# Schematics_PCB.net
KiCad netlist of a schematic drawn in EAGLE
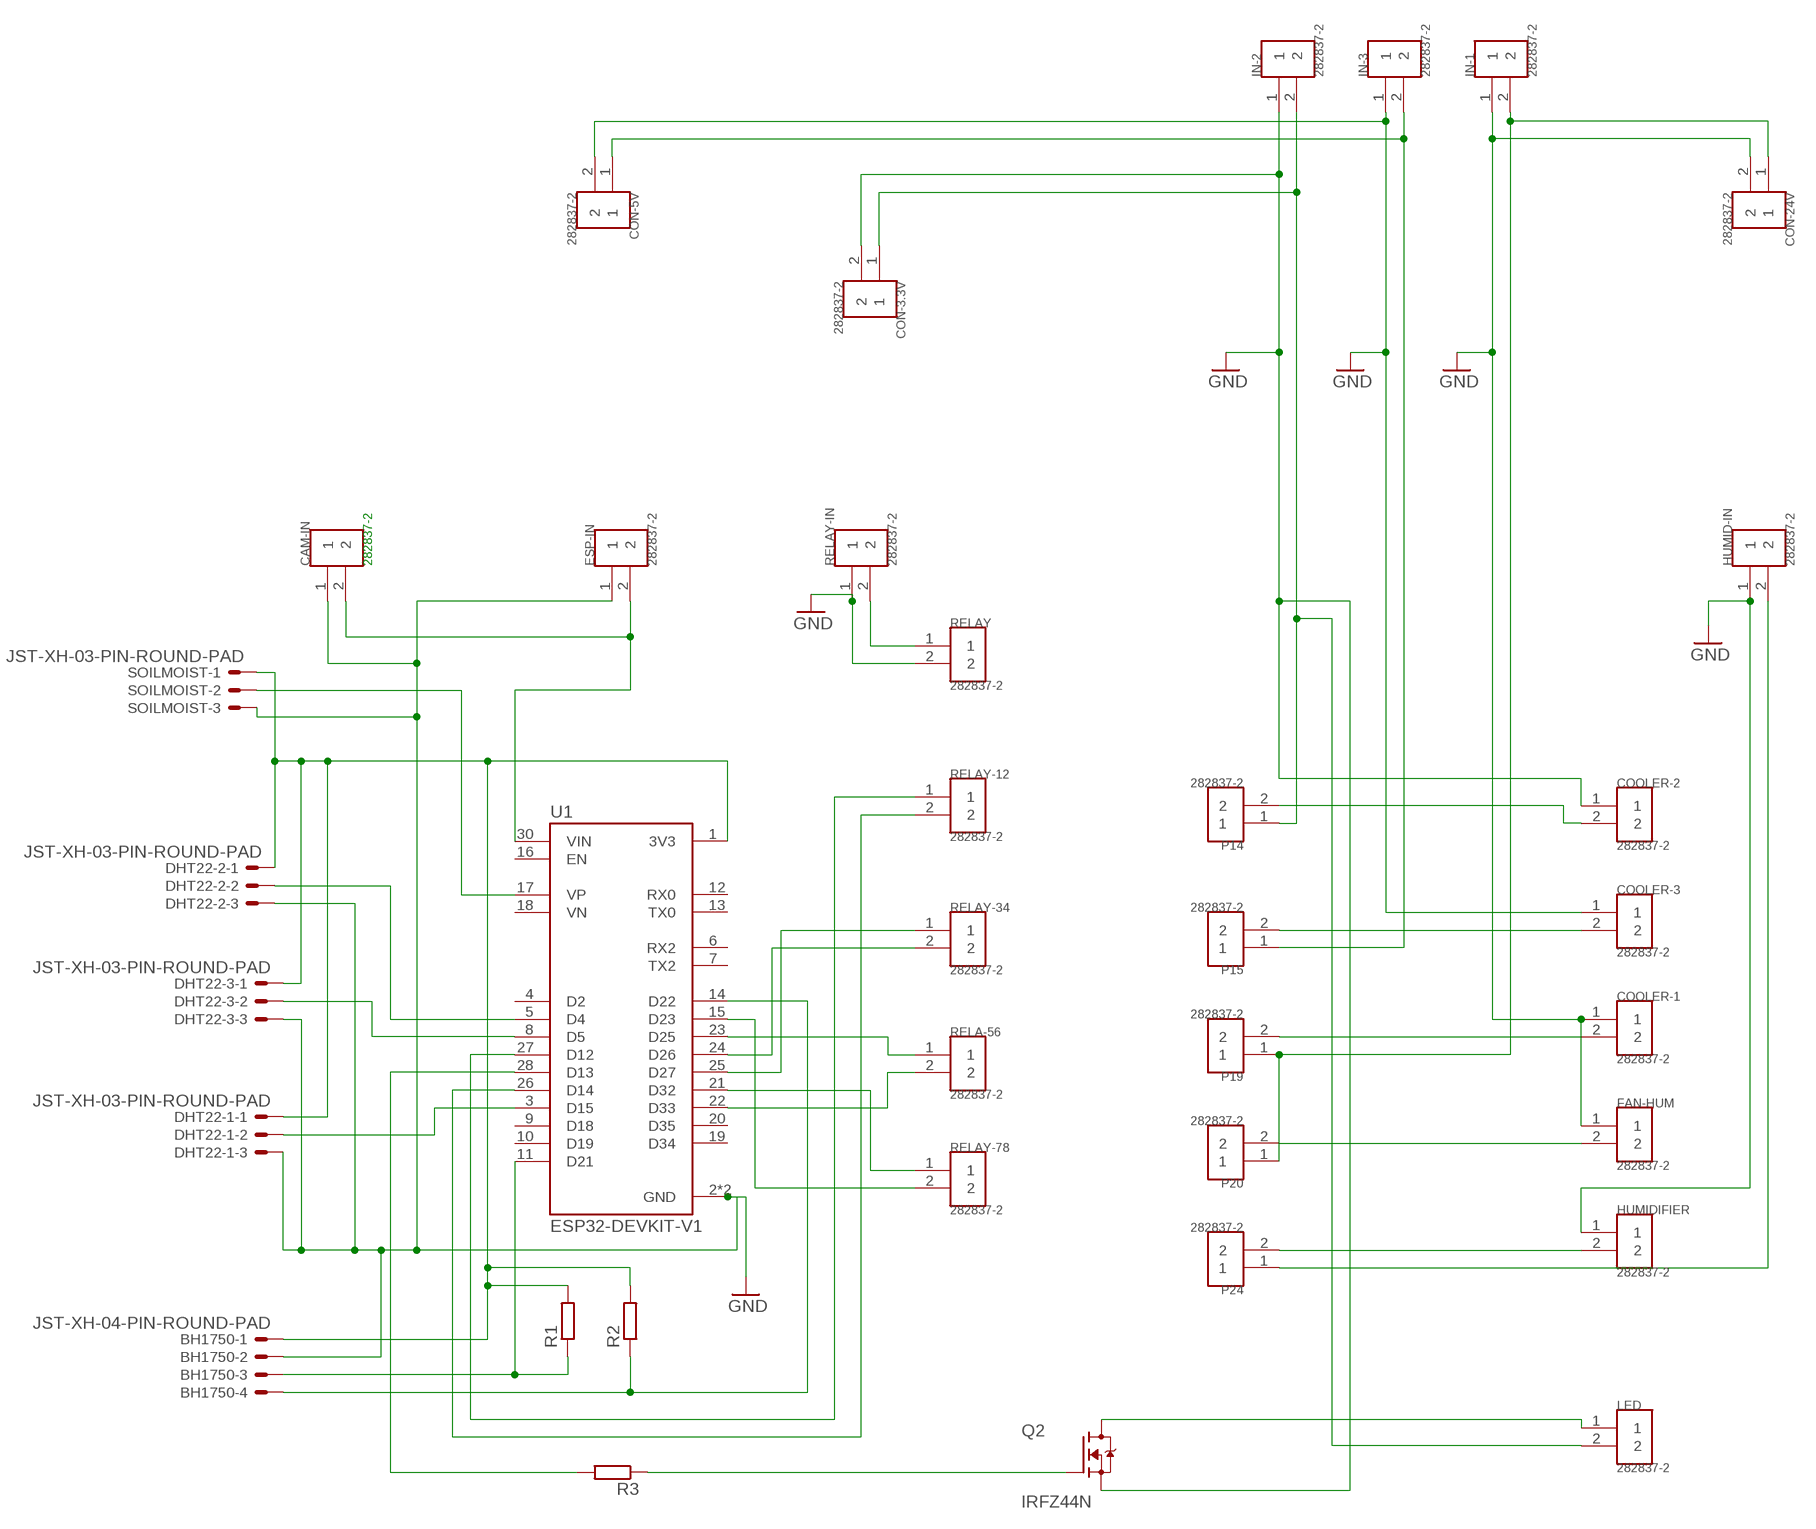
[diagram p0: schematic, sheet 1]

(export (version "E")
  (design (tool "Eeschema 10.0.6"))
  (components
    (comp (ref "BH1750")
      (value "JST-XH-04-PIN-ROUND-PAD")
      (footprint "eagle-import:JST-XH-04-PACKAGE-ROUND-PAD")
      (libsource (lib "eagle-import") (part "JST-XH-04-PIN-ROUND-PAD"))
    )
    (comp (ref "CAM-IN")
      (value "282837-2")
      (footprint "eagle-import:TE_282837-2")
      (fields (field (name "MF") "TE Connectivity"))
      (libsource (lib "eagle-import") (part "282837-2"))
    )
    (comp (ref "CON-3.3V")
      (value "282837-2")
      (footprint "eagle-import:TE_282837-2")
      (fields (field (name "MF") "TE Connectivity"))
      (libsource (lib "eagle-import") (part "282837-2"))
    )
    (comp (ref "CON-5V")
      (value "282837-2")
      (footprint "eagle-import:TE_282837-2")
      (fields (field (name "MF") "TE Connectivity"))
      (libsource (lib "eagle-import") (part "282837-2"))
    )
    (comp (ref "CON-24V")
      (value "282837-2")
      (footprint "eagle-import:TE_282837-2")
      (fields (field (name "MF") "TE Connectivity"))
      (libsource (lib "eagle-import") (part "282837-2"))
    )
    (comp (ref "COOLER-1")
      (value "282837-2")
      (footprint "eagle-import:TE_282837-2")
      (fields (field (name "MF") "TE Connectivity"))
      (libsource (lib "eagle-import") (part "282837-2"))
    )
    (comp (ref "COOLER-2")
      (value "282837-2")
      (footprint "eagle-import:TE_282837-2")
      (fields (field (name "MF") "TE Connectivity"))
      (libsource (lib "eagle-import") (part "282837-2"))
    )
    (comp (ref "COOLER-3")
      (value "282837-2")
      (footprint "eagle-import:TE_282837-2")
      (fields (field (name "MF") "TE Connectivity"))
      (libsource (lib "eagle-import") (part "282837-2"))
    )
    (comp (ref "DHT22-1")
      (value "JST-XH-03-PIN-ROUND-PAD")
      (footprint "eagle-import:JST-XH-03-PACKAGE-ROUND-PAD")
      (libsource (lib "eagle-import") (part "JST-XH-03-PIN-ROUND-PAD"))
    )
    (comp (ref "DHT22-2")
      (value "JST-XH-03-PIN-ROUND-PAD")
      (footprint "eagle-import:JST-XH-03-PACKAGE-ROUND-PAD")
      (libsource (lib "eagle-import") (part "JST-XH-03-PIN-ROUND-PAD"))
    )
    (comp (ref "DHT22-3")
      (value "JST-XH-03-PIN-ROUND-PAD")
      (footprint "eagle-import:JST-XH-03-PACKAGE-ROUND-PAD")
      (libsource (lib "eagle-import") (part "JST-XH-03-PIN-ROUND-PAD"))
    )
    (comp (ref "ESP-IN")
      (value "282837-2")
      (footprint "eagle-import:TE_282837-2")
      (fields (field (name "MF") "TE Connectivity"))
      (libsource (lib "eagle-import") (part "282837-2"))
    )
    (comp (ref "FAN-HUM")
      (value "282837-2")
      (footprint "eagle-import:TE_282837-2")
      (fields (field (name "MF") "TE Connectivity"))
      (libsource (lib "eagle-import") (part "282837-2"))
    )
    (comp (ref "HUMID-IN")
      (value "282837-2")
      (footprint "eagle-import:TE_282837-2")
      (fields (field (name "MF") "TE Connectivity"))
      (libsource (lib "eagle-import") (part "282837-2"))
    )
    (comp (ref "HUMIDIFIER")
      (value "282837-2")
      (footprint "eagle-import:TE_282837-2")
      (fields (field (name "MF") "TE Connectivity"))
      (libsource (lib "eagle-import") (part "282837-2"))
    )
    (comp (ref "IN-1")
      (value "282837-2")
      (footprint "eagle-import:TE_282837-2")
      (fields (field (name "MF") "TE Connectivity"))
      (libsource (lib "eagle-import") (part "282837-2"))
    )
    (comp (ref "IN-2")
      (value "282837-2")
      (footprint "eagle-import:TE_282837-2")
      (fields (field (name "MF") "TE Connectivity"))
      (libsource (lib "eagle-import") (part "282837-2"))
    )
    (comp (ref "IN-3")
      (value "282837-2")
      (footprint "eagle-import:TE_282837-2")
      (fields (field (name "MF") "TE Connectivity"))
      (libsource (lib "eagle-import") (part "282837-2"))
    )
    (comp (ref "LED")
      (value "282837-2")
      (footprint "eagle-import:TE_282837-2")
      (fields (field (name "MF") "TE Connectivity"))
      (libsource (lib "eagle-import") (part "282837-2"))
    )
    (comp (ref "P14")
      (value "282837-2")
      (footprint "eagle-import:TE_282837-2")
      (fields (field (name "MF") "TE Connectivity"))
      (libsource (lib "eagle-import") (part "282837-2"))
    )
    (comp (ref "P15")
      (value "282837-2")
      (footprint "eagle-import:TE_282837-2")
      (fields (field (name "MF") "TE Connectivity"))
      (libsource (lib "eagle-import") (part "282837-2"))
    )
    (comp (ref "P19")
      (value "282837-2")
      (footprint "eagle-import:TE_282837-2")
      (fields (field (name "MF") "TE Connectivity"))
      (libsource (lib "eagle-import") (part "282837-2"))
    )
    (comp (ref "P20")
      (value "282837-2")
      (footprint "eagle-import:TE_282837-2")
      (fields (field (name "MF") "TE Connectivity"))
      (libsource (lib "eagle-import") (part "282837-2"))
    )
    (comp (ref "P24")
      (value "282837-2")
      (footprint "eagle-import:TE_282837-2")
      (fields (field (name "MF") "TE Connectivity"))
      (libsource (lib "eagle-import") (part "282837-2"))
    )
    (comp (ref "Q2")
      (value "IRFZ44N")
      (footprint "eagle-import:TO254P1016X419X2286-3")
      (fields (field (name "MF") "Infineon Technologies"))
      (libsource (lib "eagle-import") (part "IRFZ44N"))
    )
    (comp (ref "R1")
      (value "R-EU_0207/10")
      (footprint "eagle-import:0207_10")
      (libsource (lib "eagle-import") (part "R-EU_0207/10"))
    )
    (comp (ref "R2")
      (value "R-EU_0207/10")
      (footprint "eagle-import:0207_10")
      (libsource (lib "eagle-import") (part "R-EU_0207/10"))
    )
    (comp (ref "R3")
      (value "R-EU_0207/10")
      (footprint "eagle-import:0207_10")
      (libsource (lib "eagle-import") (part "R-EU_0207/10"))
    )
    (comp (ref "RELA-56")
      (value "282837-2")
      (footprint "eagle-import:TE_282837-2")
      (fields (field (name "MF") "TE Connectivity"))
      (libsource (lib "eagle-import") (part "282837-2"))
    )
    (comp (ref "RELAY")
      (value "282837-2")
      (footprint "eagle-import:TE_282837-2")
      (fields (field (name "MF") "TE Connectivity"))
      (libsource (lib "eagle-import") (part "282837-2"))
    )
    (comp (ref "RELAY-12")
      (value "282837-2")
      (footprint "eagle-import:TE_282837-2")
      (fields (field (name "MF") "TE Connectivity"))
      (libsource (lib "eagle-import") (part "282837-2"))
    )
    (comp (ref "RELAY-34")
      (value "282837-2")
      (footprint "eagle-import:TE_282837-2")
      (fields (field (name "MF") "TE Connectivity"))
      (libsource (lib "eagle-import") (part "282837-2"))
    )
    (comp (ref "RELAY-78")
      (value "282837-2")
      (footprint "eagle-import:TE_282837-2")
      (fields (field (name "MF") "TE Connectivity"))
      (libsource (lib "eagle-import") (part "282837-2"))
    )
    (comp (ref "RELAY-IN")
      (value "282837-2")
      (footprint "eagle-import:TE_282837-2")
      (fields (field (name "MF") "TE Connectivity"))
      (libsource (lib "eagle-import") (part "282837-2"))
    )
    (comp (ref "SOILMOIST")
      (value "JST-XH-03-PIN-ROUND-PAD")
      (footprint "eagle-import:JST-XH-03-PACKAGE-ROUND-PAD")
      (libsource (lib "eagle-import") (part "JST-XH-03-PIN-ROUND-PAD"))
    )
    (comp (ref "U1")
      (value "ESP32-DEVKIT-V1")
      (footprint "eagle-import:MODULE_ESP32_DEVKIT_V1")
      (fields (field (name "MF") "Do it"))
      (libsource (lib "eagle-import") (part "ESP32-DEVKIT-V1"))
    )
  )
  (nets
    (net (code "1") (name "GND") (class "Default")
      (node (ref "BH1750") (pin "2") (pinfunction "S_2") (pintype "passive"))
      (node (ref "CAM-IN") (pin "1") (pinfunction "1_1") (pintype "passive"))
      (node (ref "CON-24V") (pin "2") (pinfunction "2_2") (pintype "passive"))
      (node (ref "CON-3.3V") (pin "2") (pinfunction "2_2") (pintype "passive"))
      (node (ref "CON-5V") (pin "2") (pinfunction "2_2") (pintype "passive"))
      (node (ref "COOLER-1") (pin "1") (pinfunction "1_1") (pintype "passive"))
      (node (ref "COOLER-2") (pin "1") (pinfunction "1_1") (pintype "passive"))
      (node (ref "COOLER-3") (pin "1") (pinfunction "1_1") (pintype "passive"))
      (node (ref "DHT22-1") (pin "3") (pinfunction "S_3") (pintype "passive"))
      (node (ref "DHT22-2") (pin "3") (pinfunction "S_3") (pintype "passive"))
      (node (ref "DHT22-3") (pin "3") (pinfunction "S_3") (pintype "passive"))
      (node (ref "ESP-IN") (pin "1") (pinfunction "1_1") (pintype "passive"))
      (node (ref "FAN-HUM") (pin "1") (pinfunction "1_1") (pintype "passive"))
      (node (ref "HUMID-IN") (pin "1") (pinfunction "1_1") (pintype "passive"))
      (node (ref "HUMIDIFIER") (pin "1") (pinfunction "1_1") (pintype "passive"))
      (node (ref "IN-1") (pin "1") (pinfunction "1_1") (pintype "passive"))
      (node (ref "IN-2") (pin "1") (pinfunction "1_1") (pintype "passive"))
      (node (ref "IN-3") (pin "1") (pinfunction "1_1") (pintype "passive"))
      (node (ref "Q2") (pin "3") (pinfunction "S_3") (pintype "passive"))
      (node (ref "RELAY") (pin "2") (pinfunction "2_2") (pintype "passive"))
      (node (ref "RELAY-IN") (pin "1") (pinfunction "1_1") (pintype "passive"))
      (node (ref "SOILMOIST") (pin "3") (pinfunction "S_3") (pintype "passive"))
      (node (ref "U1") (pin "2") (pinfunction "GND_2") (pintype "power_in"))
      (node (ref "U1") (pin "29") (pinfunction "GND_29") (pintype "power_in"))
    )
    (net (code "2") (name "Net-(BH1750A-S)") (class "Default")
      (node (ref "BH1750") (pin "1") (pinfunction "S_1") (pintype "passive"))
      (node (ref "DHT22-1") (pin "1") (pinfunction "S_1") (pintype "passive"))
      (node (ref "DHT22-2") (pin "1") (pinfunction "S_1") (pintype "passive"))
      (node (ref "DHT22-3") (pin "1") (pinfunction "S_1") (pintype "passive"))
      (node (ref "R1") (pin "2") (pinfunction "2_2") (pintype "passive"))
      (node (ref "R2") (pin "2") (pinfunction "2_2") (pintype "passive"))
      (node (ref "SOILMOIST") (pin "1") (pinfunction "S_1") (pintype "passive"))
      (node (ref "U1") (pin "1") (pinfunction "3V3_1") (pintype "output"))
    )
    (net (code "3") (name "Net-(BH1750C-S)") (class "Default")
      (node (ref "BH1750") (pin "3") (pinfunction "S_3") (pintype "passive"))
      (node (ref "R1") (pin "1") (pinfunction "1_1") (pintype "passive"))
      (node (ref "U1") (pin "11") (pinfunction "D21_11") (pintype "bidirectional"))
    )
    (net (code "4") (name "Net-(BH1750D-S)") (class "Default")
      (node (ref "BH1750") (pin "4") (pinfunction "S_4") (pintype "passive"))
      (node (ref "R2") (pin "1") (pinfunction "1_1") (pintype "passive"))
      (node (ref "U1") (pin "14") (pinfunction "D22_14") (pintype "bidirectional"))
    )
    (net (code "5") (name "Net-(CON-3.3V-Pad1)") (class "Default")
      (node (ref "CON-3.3V") (pin "1") (pinfunction "1_1") (pintype "passive"))
      (node (ref "IN-2") (pin "2") (pinfunction "2_2") (pintype "passive"))
      (node (ref "LED") (pin "2") (pinfunction "2_2") (pintype "passive"))
      (node (ref "P14") (pin "1") (pinfunction "1_1") (pintype "passive"))
    )
    (net (code "6") (name "Net-(CON-5V-Pad1)") (class "Default")
      (node (ref "CON-5V") (pin "1") (pinfunction "1_1") (pintype "passive"))
      (node (ref "IN-3") (pin "2") (pinfunction "2_2") (pintype "passive"))
      (node (ref "P15") (pin "1") (pinfunction "1_1") (pintype "passive"))
    )
    (net (code "7") (name "Net-(CON-24V-Pad1)") (class "Default")
      (node (ref "CON-24V") (pin "1") (pinfunction "1_1") (pintype "passive"))
      (node (ref "IN-1") (pin "2") (pinfunction "2_2") (pintype "passive"))
      (node (ref "P19") (pin "1") (pinfunction "1_1") (pintype "passive"))
      (node (ref "P20") (pin "1") (pinfunction "1_1") (pintype "passive"))
    )
    (net (code "8") (name "Net-(COOLER-1-Pad2)") (class "Default")
      (node (ref "COOLER-1") (pin "2") (pinfunction "2_2") (pintype "passive"))
      (node (ref "P19") (pin "2") (pinfunction "2_2") (pintype "passive"))
    )
    (net (code "9") (name "Net-(COOLER-2-Pad2)") (class "Default")
      (node (ref "COOLER-2") (pin "2") (pinfunction "2_2") (pintype "passive"))
      (node (ref "P14") (pin "2") (pinfunction "2_2") (pintype "passive"))
    )
    (net (code "10") (name "Net-(COOLER-3-Pad2)") (class "Default")
      (node (ref "COOLER-3") (pin "2") (pinfunction "2_2") (pintype "passive"))
      (node (ref "P15") (pin "2") (pinfunction "2_2") (pintype "passive"))
    )
    (net (code "11") (name "Net-(DHT22-1B-S)") (class "Default")
      (node (ref "DHT22-1") (pin "2") (pinfunction "S_2") (pintype "passive"))
      (node (ref "U1") (pin "3") (pinfunction "D15_3") (pintype "bidirectional"))
    )
    (net (code "12") (name "Net-(DHT22-2B-S)") (class "Default")
      (node (ref "DHT22-2") (pin "2") (pinfunction "S_2") (pintype "passive"))
      (node (ref "U1") (pin "5") (pinfunction "D4_5") (pintype "bidirectional"))
    )
    (net (code "13") (name "Net-(DHT22-3B-S)") (class "Default")
      (node (ref "DHT22-3") (pin "2") (pinfunction "S_2") (pintype "passive"))
      (node (ref "U1") (pin "8") (pinfunction "D5_8") (pintype "bidirectional"))
    )
    (net (code "14") (name "Net-(FAN-HUM-Pad2)") (class "Default")
      (node (ref "FAN-HUM") (pin "2") (pinfunction "2_2") (pintype "passive"))
      (node (ref "P20") (pin "2") (pinfunction "2_2") (pintype "passive"))
    )
    (net (code "15") (name "Net-(HUMID-IN-Pad2)") (class "Default")
      (node (ref "HUMID-IN") (pin "2") (pinfunction "2_2") (pintype "passive"))
      (node (ref "P24") (pin "1") (pinfunction "1_1") (pintype "passive"))
    )
    (net (code "16") (name "Net-(HUMIDIFIER-Pad2)") (class "Default")
      (node (ref "HUMIDIFIER") (pin "2") (pinfunction "2_2") (pintype "passive"))
      (node (ref "P24") (pin "2") (pinfunction "2_2") (pintype "passive"))
    )
    (net (code "17") (name "Net-(Q2-D)") (class "Default")
      (node (ref "LED") (pin "1") (pinfunction "1_1") (pintype "passive"))
      (node (ref "Q2") (pin "2") (pinfunction "D_2") (pintype "passive"))
    )
    (net (code "18") (name "Net-(Q2-G)") (class "Default")
      (node (ref "Q2") (pin "1") (pinfunction "G_1") (pintype "passive"))
      (node (ref "R3") (pin "1") (pinfunction "1_1") (pintype "passive"))
    )
    (net (code "19") (name "Net-(RELAY-IN-Pad2)") (class "Default")
      (node (ref "RELAY") (pin "1") (pinfunction "1_1") (pintype "passive"))
      (node (ref "RELAY-IN") (pin "2") (pinfunction "2_2") (pintype "passive"))
    )
    (net (code "20") (name "Net-(SOILMOISTB-S)") (class "Default")
      (node (ref "SOILMOIST") (pin "2") (pinfunction "S_2") (pintype "passive"))
      (node (ref "U1") (pin "17") (pinfunction "VP_17") (pintype "bidirectional"))
    )
    (net (code "21") (name "Net-(U1-D12)") (class "Default")
      (node (ref "RELAY-12") (pin "1") (pinfunction "1_1") (pintype "passive"))
      (node (ref "U1") (pin "27") (pinfunction "D12_27") (pintype "bidirectional"))
    )
    (net (code "22") (name "Net-(U1-D13)") (class "Default")
      (node (ref "R3") (pin "2") (pinfunction "2_2") (pintype "passive"))
      (node (ref "U1") (pin "28") (pinfunction "D13_28") (pintype "bidirectional"))
    )
    (net (code "23") (name "Net-(U1-D14)") (class "Default")
      (node (ref "RELAY-12") (pin "2") (pinfunction "2_2") (pintype "passive"))
      (node (ref "U1") (pin "26") (pinfunction "D14_26") (pintype "bidirectional"))
    )
    (net (code "24") (name "Net-(U1-D23)") (class "Default")
      (node (ref "RELAY-78") (pin "2") (pinfunction "2_2") (pintype "passive"))
      (node (ref "U1") (pin "15") (pinfunction "D23_15") (pintype "bidirectional"))
    )
    (net (code "25") (name "Net-(U1-D25)") (class "Default")
      (node (ref "RELA-56") (pin "1") (pinfunction "1_1") (pintype "passive"))
      (node (ref "U1") (pin "23") (pinfunction "D25_23") (pintype "bidirectional"))
    )
    (net (code "26") (name "Net-(U1-D26)") (class "Default")
      (node (ref "RELAY-34") (pin "2") (pinfunction "2_2") (pintype "passive"))
      (node (ref "U1") (pin "24") (pinfunction "D26_24") (pintype "bidirectional"))
    )
    (net (code "27") (name "Net-(U1-D27)") (class "Default")
      (node (ref "RELAY-34") (pin "1") (pinfunction "1_1") (pintype "passive"))
      (node (ref "U1") (pin "25") (pinfunction "D27_25") (pintype "bidirectional"))
    )
    (net (code "28") (name "Net-(U1-D32)") (class "Default")
      (node (ref "RELAY-78") (pin "1") (pinfunction "1_1") (pintype "passive"))
      (node (ref "U1") (pin "21") (pinfunction "D32_21") (pintype "bidirectional"))
    )
    (net (code "29") (name "Net-(U1-D33)") (class "Default")
      (node (ref "RELA-56") (pin "2") (pinfunction "2_2") (pintype "passive"))
      (node (ref "U1") (pin "22") (pinfunction "D33_22") (pintype "bidirectional"))
    )
    (net (code "30") (name "Net-(U1-VIN)") (class "Default")
      (node (ref "CAM-IN") (pin "2") (pinfunction "2_2") (pintype "passive"))
      (node (ref "ESP-IN") (pin "2") (pinfunction "2_2") (pintype "passive"))
      (node (ref "U1") (pin "30") (pinfunction "VIN_30") (pintype "input"))
    )
    (net (code "31") (name "unconnected-(U1-D2-Pad4)") (class "Default")
      (node (ref "U1") (pin "4") (pinfunction "D2_4") (pintype "bidirectional"))
    )
    (net (code "32") (name "unconnected-(U1-D18-Pad9)") (class "Default")
      (node (ref "U1") (pin "9") (pinfunction "D18_9") (pintype "bidirectional"))
    )
    (net (code "33") (name "unconnected-(U1-D19-Pad10)") (class "Default")
      (node (ref "U1") (pin "10") (pinfunction "D19_10") (pintype "bidirectional"))
    )
    (net (code "34") (name "unconnected-(U1-D34-Pad19)") (class "Default")
      (node (ref "U1") (pin "19") (pinfunction "D34_19") (pintype "bidirectional"))
    )
    (net (code "35") (name "unconnected-(U1-D35-Pad20)") (class "Default")
      (node (ref "U1") (pin "20") (pinfunction "D35_20") (pintype "bidirectional"))
    )
    (net (code "36") (name "unconnected-(U1-EN-Pad16)") (class "Default")
      (node (ref "U1") (pin "16") (pinfunction "EN_16") (pintype "input"))
    )
    (net (code "37") (name "unconnected-(U1-RX0-Pad12)") (class "Default")
      (node (ref "U1") (pin "12") (pinfunction "RX0_12") (pintype "input"))
    )
    (net (code "38") (name "unconnected-(U1-RX2-Pad6)") (class "Default")
      (node (ref "U1") (pin "6") (pinfunction "RX2_6") (pintype "input"))
    )
    (net (code "39") (name "unconnected-(U1-TX0-Pad13)") (class "Default")
      (node (ref "U1") (pin "13") (pinfunction "TX0_13") (pintype "output"))
    )
    (net (code "40") (name "unconnected-(U1-TX2-Pad7)") (class "Default")
      (node (ref "U1") (pin "7") (pinfunction "TX2_7") (pintype "output"))
    )
    (net (code "41") (name "unconnected-(U1-VN-Pad18)") (class "Default")
      (node (ref "U1") (pin "18") (pinfunction "VN_18") (pintype "bidirectional"))
    )
  )
)
